# schmatic.net
KiCad netlist of a schematic drawn in EAGLE
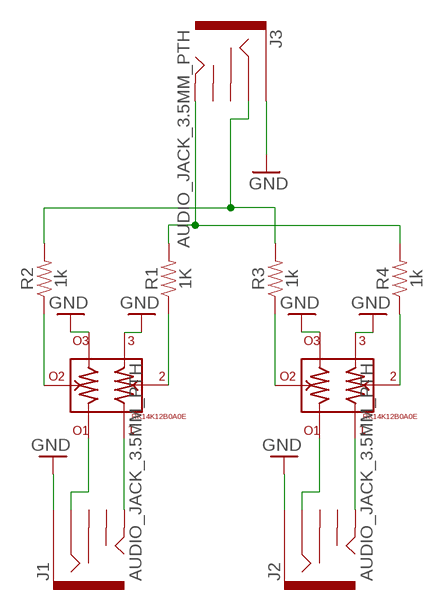
[diagram p0: schematic, sheet 1]

(export (version "E")
  (design (tool "Eeschema 10.0.6"))
  (components
    (comp (ref "J1")
      (value "AUDIO_JACK_3.5MM_PTH")
      (footprint "eagle-import:AUDIO-JACK")
      (libsource (lib "eagle-import") (part "AUDIO_JACK_3.5MM_PTH"))
    )
    (comp (ref "J2")
      (value "AUDIO_JACK_3.5MM_PTH")
      (footprint "eagle-import:AUDIO-JACK")
      (libsource (lib "eagle-import") (part "AUDIO_JACK_3.5MM_PTH"))
    )
    (comp (ref "J3")
      (value "AUDIO_JACK_3.5MM_PTH")
      (footprint "eagle-import:AUDIO-JACK")
      (libsource (lib "eagle-import") (part "AUDIO_JACK_3.5MM_PTH"))
    )
    (comp (ref "POT01")
      (value "RK14K12B0A0E")
      (footprint "eagle-import:RK14K12B0A0E")
      (libsource (lib "eagle-import") (part "RK14K12B0A0E"))
    )
    (comp (ref "POT02")
      (value "RK14K12B0A0E")
      (footprint "eagle-import:RK14K12B0A0E")
      (libsource (lib "eagle-import") (part "RK14K12B0A0E"))
    )
    (comp (ref "R1")
      (value "1K")
      (footprint "eagle-import:AXIAL-0.3")
      (libsource (lib "eagle-import") (part "10MOHM-HORIZ-1/4W-5%"))
    )
    (comp (ref "R2")
      (value "1k")
      (footprint "eagle-import:AXIAL-0.3")
      (libsource (lib "eagle-import") (part "10MOHM-HORIZ-1/4W-5%"))
    )
    (comp (ref "R3")
      (value "1k")
      (footprint "eagle-import:AXIAL-0.3")
      (libsource (lib "eagle-import") (part "10MOHM-HORIZ-1/4W-5%"))
    )
    (comp (ref "R4")
      (value "1k")
      (footprint "eagle-import:AXIAL-0.3")
      (libsource (lib "eagle-import") (part "10MOHM-HORIZ-1/4W-5%"))
    )
  )
  (nets
    (net (code "1") (name "GND") (class "Default")
      (node (ref "J1") (pin "SLEEVE") (pinfunction "SLEEVE_SLEEVE") (pintype "bidirectional"))
      (node (ref "J2") (pin "SLEEVE") (pinfunction "SLEEVE_SLEEVE") (pintype "bidirectional"))
      (node (ref "J3") (pin "SLEEVE") (pinfunction "SLEEVE_SLEEVE") (pintype "bidirectional"))
      (node (ref "POT01") (pin "3") (pinfunction "3_3") (pintype "bidirectional"))
      (node (ref "POT01") (pin "O3") (pinfunction "O3_O3") (pintype "bidirectional"))
      (node (ref "POT02") (pin "3") (pinfunction "3_3") (pintype "bidirectional"))
      (node (ref "POT02") (pin "O3") (pinfunction "O3_O3") (pintype "bidirectional"))
    )
    (net (code "2") (name "Net-(J1-PadRING)") (class "Default")
      (node (ref "J1") (pin "RING") (pinfunction "RING_RING") (pintype "bidirectional"))
      (node (ref "POT02") (pin "O1") (pinfunction "O1_O1") (pintype "bidirectional"))
    )
    (net (code "3") (name "Net-(J1-PadTIP)") (class "Default")
      (node (ref "J1") (pin "TIP") (pinfunction "TIP_TIP") (pintype "bidirectional"))
      (node (ref "POT02") (pin "1") (pinfunction "1_1") (pintype "bidirectional"))
    )
    (net (code "4") (name "Net-(J2-PadRING)") (class "Default")
      (node (ref "J2") (pin "RING") (pinfunction "RING_RING") (pintype "bidirectional"))
      (node (ref "POT01") (pin "O1") (pinfunction "O1_O1") (pintype "bidirectional"))
    )
    (net (code "5") (name "Net-(J2-PadTIP)") (class "Default")
      (node (ref "J2") (pin "TIP") (pinfunction "TIP_TIP") (pintype "bidirectional"))
      (node (ref "POT01") (pin "1") (pinfunction "1_1") (pintype "bidirectional"))
    )
    (net (code "6") (name "Net-(R1-1)") (class "Default")
      (node (ref "POT02") (pin "2") (pinfunction "2_2") (pintype "bidirectional"))
      (node (ref "R1") (pin "P$1") (pinfunction "1_P$1") (pintype "passive"))
    )
    (net (code "7") (name "Net-(R1-2)") (class "Default")
      (node (ref "J3") (pin "TIP") (pinfunction "TIP_TIP") (pintype "bidirectional"))
      (node (ref "R1") (pin "P$2") (pinfunction "2_P$2") (pintype "passive"))
      (node (ref "R4") (pin "P$2") (pinfunction "2_P$2") (pintype "passive"))
    )
    (net (code "8") (name "Net-(R2-1)") (class "Default")
      (node (ref "POT02") (pin "O2") (pinfunction "O2_O2") (pintype "bidirectional"))
      (node (ref "R2") (pin "P$1") (pinfunction "1_P$1") (pintype "passive"))
    )
    (net (code "9") (name "Net-(R2-2)") (class "Default")
      (node (ref "J3") (pin "RING") (pinfunction "RING_RING") (pintype "bidirectional"))
      (node (ref "R2") (pin "P$2") (pinfunction "2_P$2") (pintype "passive"))
      (node (ref "R3") (pin "P$2") (pinfunction "2_P$2") (pintype "passive"))
    )
    (net (code "10") (name "Net-(R3-1)") (class "Default")
      (node (ref "POT01") (pin "O2") (pinfunction "O2_O2") (pintype "bidirectional"))
      (node (ref "R3") (pin "P$1") (pinfunction "1_P$1") (pintype "passive"))
    )
    (net (code "11") (name "Net-(R4-1)") (class "Default")
      (node (ref "POT01") (pin "2") (pinfunction "2_2") (pintype "bidirectional"))
      (node (ref "R4") (pin "P$1") (pinfunction "1_P$1") (pintype "passive"))
    )
    (net (code "12") (name "unconnected-(J1-PadRSH)") (class "Default")
      (node (ref "J1") (pin "RSH") (pinfunction "RSH_RSH") (pintype "bidirectional"))
    )
    (net (code "13") (name "unconnected-(J1-PadTSH)") (class "Default")
      (node (ref "J1") (pin "TSH") (pinfunction "TSH_TSH") (pintype "bidirectional"))
    )
    (net (code "14") (name "unconnected-(J2-PadRSH)") (class "Default")
      (node (ref "J2") (pin "RSH") (pinfunction "RSH_RSH") (pintype "bidirectional"))
    )
    (net (code "15") (name "unconnected-(J2-PadTSH)") (class "Default")
      (node (ref "J2") (pin "TSH") (pinfunction "TSH_TSH") (pintype "bidirectional"))
    )
    (net (code "16") (name "unconnected-(J3-PadRSH)") (class "Default")
      (node (ref "J3") (pin "RSH") (pinfunction "RSH_RSH") (pintype "bidirectional"))
    )
    (net (code "17") (name "unconnected-(J3-PadTSH)") (class "Default")
      (node (ref "J3") (pin "TSH") (pinfunction "TSH_TSH") (pintype "bidirectional"))
    )
  )
)
